# 1-Schematic_New_Project.net
KiCad netlist of a schematic drawn in EasyEDA
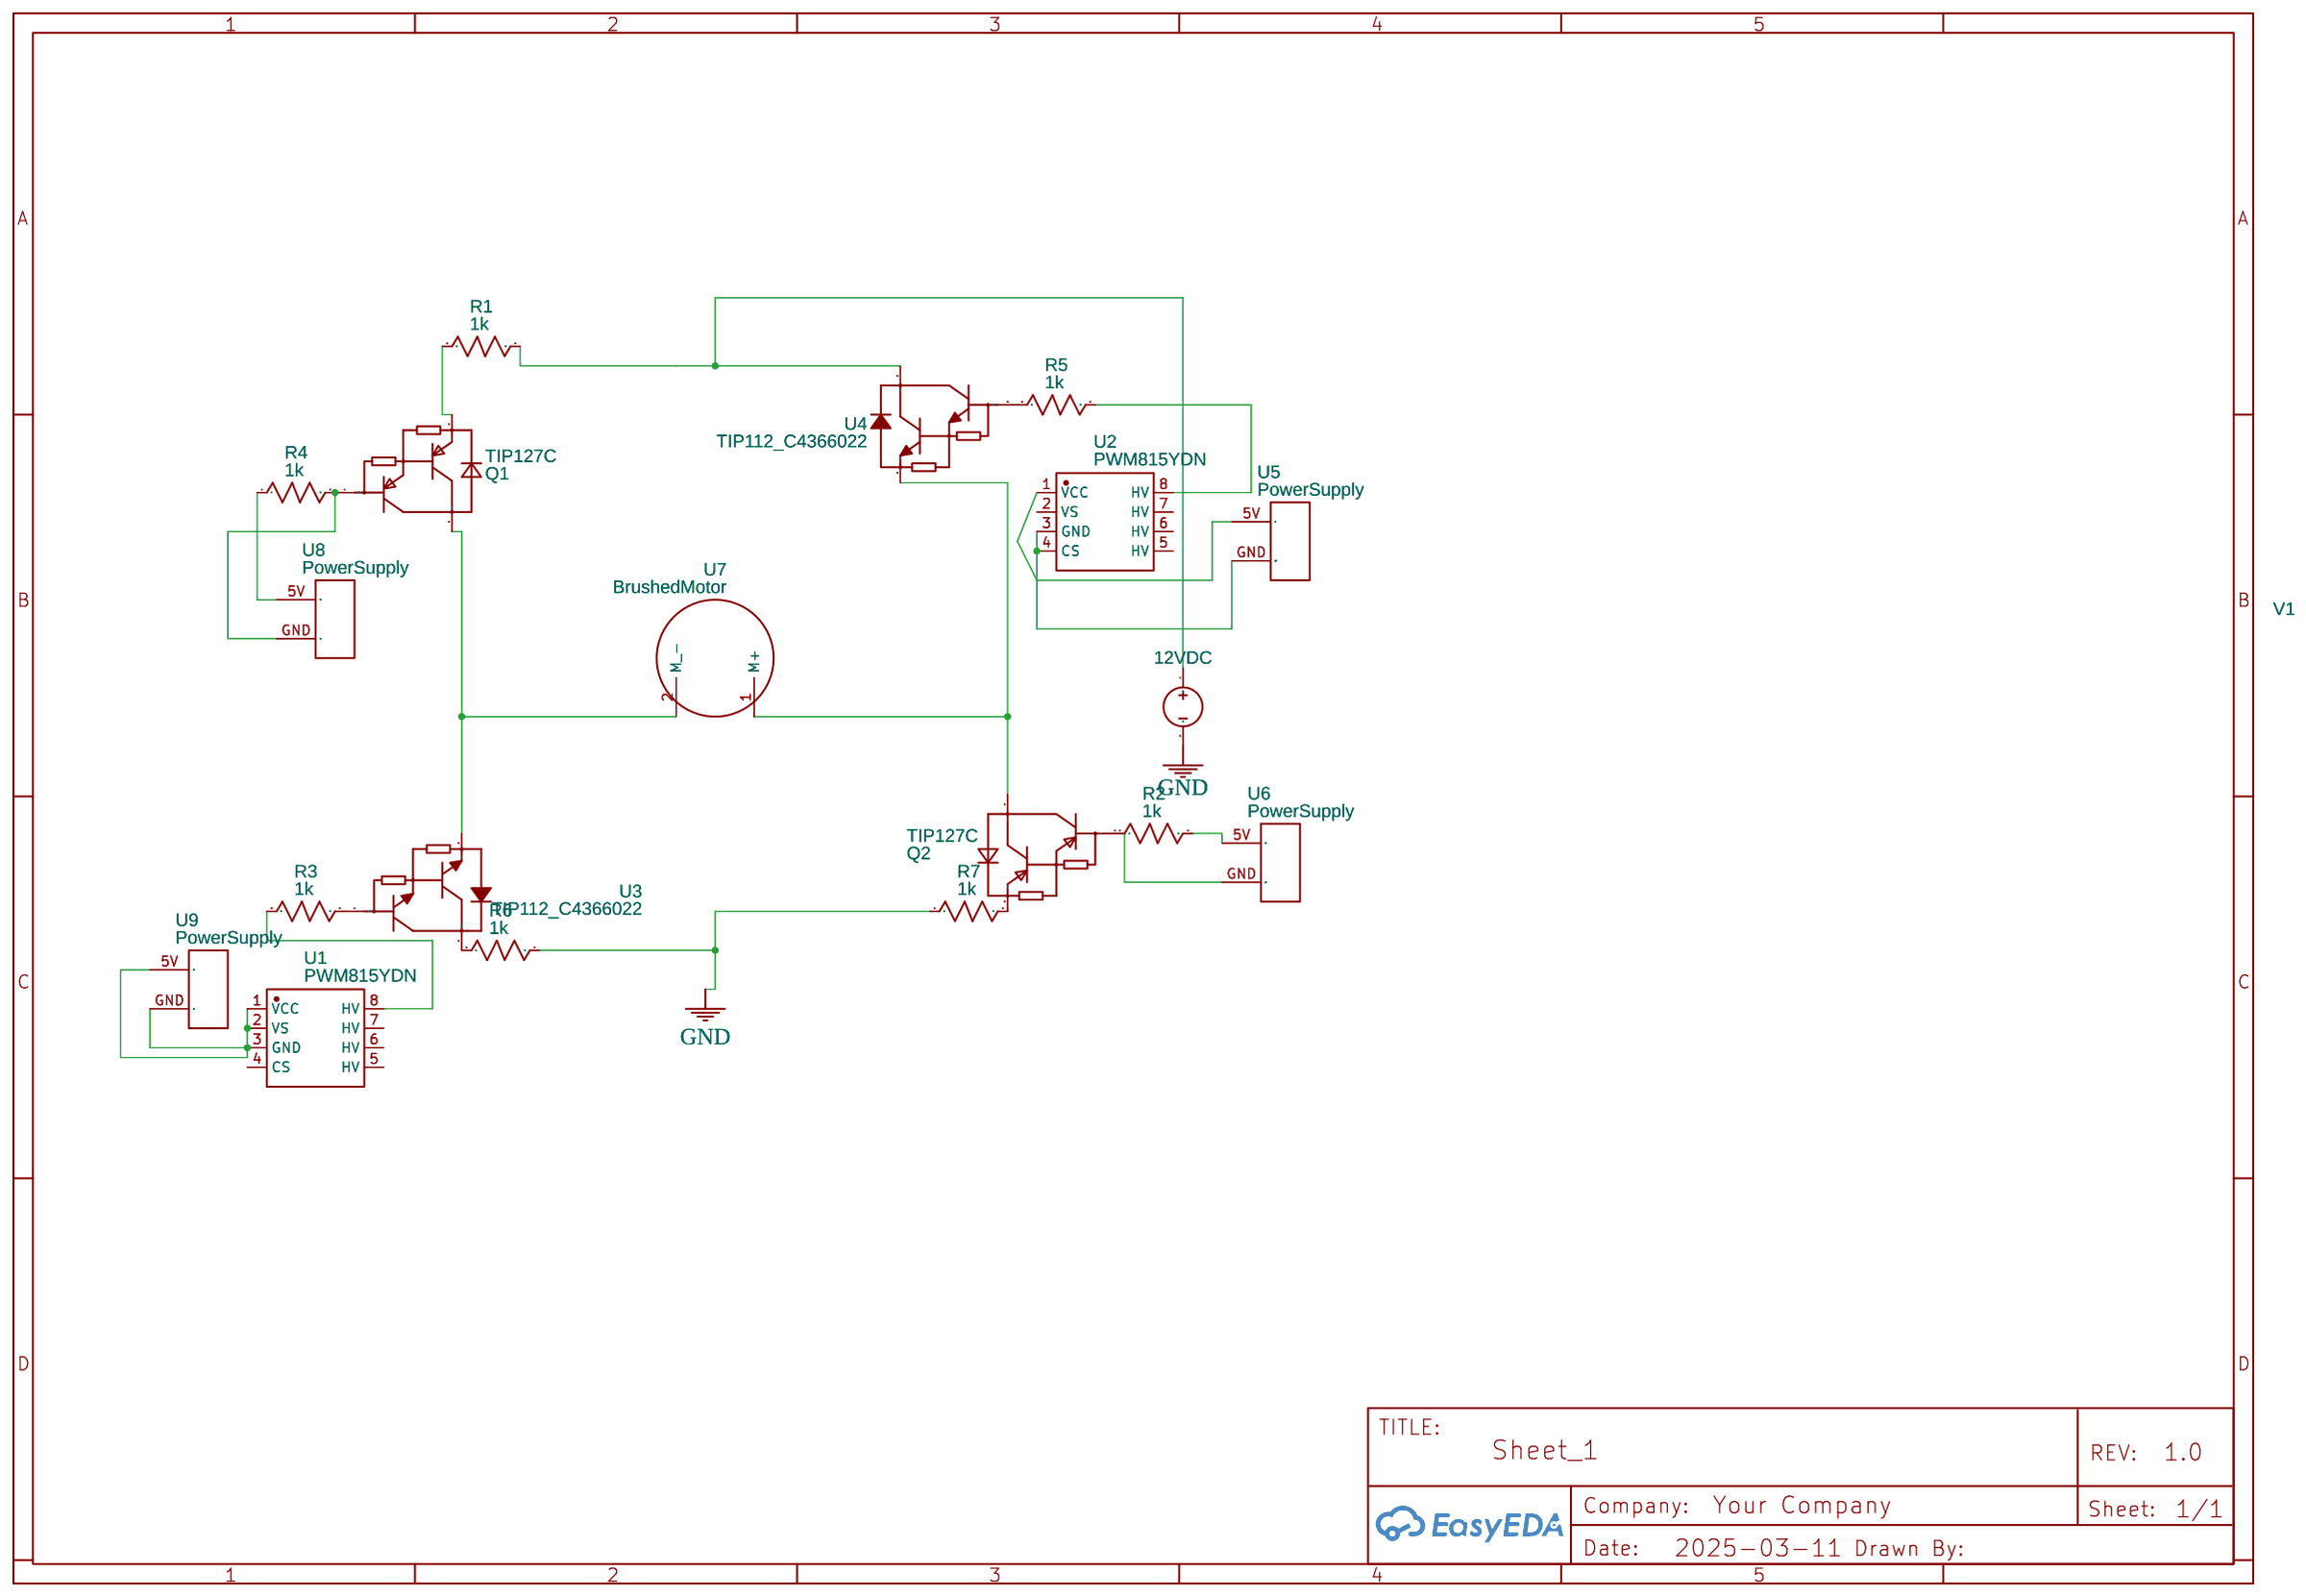
[diagram p0: schematic sheet]

(export (version "E")
  (design (tool "Eeschema 10.0.6"))
  (components
    (comp (ref "Q1")
      (value "TIP127C")
      (fields (field (name "Manufacturer") "FeiHong(飞虹)"))
      (libsource (lib "") (part "TIP127C_1"))
    )
    (comp (ref "Q2")
      (value "TIP127C")
      (fields (field (name "Manufacturer") "FeiHong(飞虹)"))
      (libsource (lib "") (part "TIP127C"))
    )
    (comp (ref "R1") (value "1k") (libsource (lib "") (part "R_0603_US")))
    (comp (ref "R2") (value "1k") (libsource (lib "") (part "R_0603_US")))
    (comp (ref "R3") (value "1k") (libsource (lib "") (part "R_0603_US")))
    (comp (ref "R4") (value "1k") (libsource (lib "") (part "R_0603_US")))
    (comp (ref "R5") (value "1k") (libsource (lib "") (part "R_0603_US")))
    (comp (ref "R6") (value "1k") (libsource (lib "") (part "R_0603_US")))
    (comp (ref "R7") (value "1k") (libsource (lib "") (part "R_0603_US")))
    (comp (ref "U1")
      (value "PWM815YDN")
      (fields (field (name "Manufacturer") "MASPOWER(麦思浦)"))
      (libsource (lib "") (part "PWM815YDN"))
    )
    (comp (ref "U2")
      (value "PWM815YDN")
      (fields (field (name "Manufacturer") "MASPOWER(麦思浦)"))
      (libsource (lib "") (part "PWM815YDN"))
    )
    (comp (ref "U3")
      (value "TIP112_C4366022")
      (fields (field (name "Manufacturer Part") "TIP112") (field (name "Manufacturer") "TI(德州仪器)"))
      (libsource (lib "") (part "TIP112_C4366022_1"))
    )
    (comp (ref "U4")
      (value "TIP112_C4366022")
      (fields (field (name "Manufacturer Part") "TIP112") (field (name "Manufacturer") "TI(德州仪器)"))
      (libsource (lib "") (part "TIP112_C4366022"))
    )
    (comp (ref "U5") (value "PowerSupply") (libsource (lib "") (part "PowerSupply")))
    (comp (ref "U6") (value "PowerSupply") (libsource (lib "") (part "PowerSupply")))
    (comp (ref "U7") (value "BrushedMotor") (libsource (lib "") (part "BrushedMotor")))
    (comp (ref "U8") (value "PowerSupply") (libsource (lib "") (part "PowerSupply")))
    (comp (ref "U9") (value "PowerSupply") (libsource (lib "") (part "PowerSupply")))
    (comp (ref "V1") (value "12VDC") (libsource (lib "") (part "Power_Supply_12V copy")))
  )
  (nets
    (net (code "1") (name "GND") (class "Default")
      (node (ref "R6") (pin "2") (pinfunction "2_2") (pintype "unspecified"))
      (node (ref "R7") (pin "1") (pinfunction "1_1") (pintype "unspecified"))
      (node (ref "V1") (pin "2") (pinfunction "2_2") (pintype "unspecified"))
    )
    (net (code "2") (name "Net-(Q1-B)") (class "Default")
      (node (ref "Q1") (pin "1") (pinfunction "B_1") (pintype "input"))
      (node (ref "R4") (pin "2") (pinfunction "2_2") (pintype "unspecified"))
      (node (ref "U8") (pin "GND") (pinfunction "GND_GND") (pintype "unspecified"))
    )
    (net (code "3") (name "Net-(Q1-C)") (class "Default")
      (node (ref "Q1") (pin "2") (pinfunction "C_2") (pintype "input"))
      (node (ref "U3") (pin "3") (pinfunction "E_3") (pintype "input"))
      (node (ref "U7") (pin "2") (pinfunction "M_-_2") (pintype "unspecified"))
    )
    (net (code "4") (name "Net-(Q1-E)") (class "Default")
      (node (ref "Q1") (pin "3") (pinfunction "E_3") (pintype "input"))
      (node (ref "R1") (pin "1") (pinfunction "1_1") (pintype "unspecified"))
    )
    (net (code "5") (name "Net-(Q2-B)") (class "Default")
      (node (ref "Q2") (pin "1") (pinfunction "B_1") (pintype "input"))
      (node (ref "U6") (pin "GND") (pinfunction "GND_GND") (pintype "unspecified"))
    )
    (net (code "6") (name "Net-(Q2-C)") (class "Default")
      (node (ref "Q2") (pin "2") (pinfunction "C_2") (pintype "input"))
      (node (ref "U4") (pin "3") (pinfunction "E_3") (pintype "input"))
      (node (ref "U7") (pin "1") (pinfunction "M+_1") (pintype "unspecified"))
    )
    (net (code "7") (name "Net-(Q2-E)") (class "Default")
      (node (ref "Q2") (pin "3") (pinfunction "E_3") (pintype "input"))
      (node (ref "R7") (pin "2") (pinfunction "2_2") (pintype "unspecified"))
    )
    (net (code "8") (name "Net-(R2-Pad2)") (class "Default")
      (node (ref "R2") (pin "2") (pinfunction "2_2") (pintype "unspecified"))
      (node (ref "U6") (pin "5V") (pinfunction "5V_5V") (pintype "unspecified"))
    )
    (net (code "9") (name "Net-(R3-Pad1)") (class "Default")
      (node (ref "R3") (pin "1") (pinfunction "1_1") (pintype "unspecified"))
      (node (ref "U1") (pin "8") (pinfunction "HV_8") (pintype "unspecified"))
    )
    (net (code "10") (name "Net-(R4-Pad1)") (class "Default")
      (node (ref "R4") (pin "1") (pinfunction "1_1") (pintype "unspecified"))
      (node (ref "U8") (pin "5V") (pinfunction "5V_5V") (pintype "unspecified"))
    )
    (net (code "11") (name "Net-(R5-Pad2)") (class "Default")
      (node (ref "R5") (pin "2") (pinfunction "2_2") (pintype "unspecified"))
      (node (ref "U2") (pin "8") (pinfunction "HV_8") (pintype "unspecified"))
    )
    (net (code "12") (name "Net-(U1-GND)") (class "Default")
      (node (ref "U1") (pin "1") (pinfunction "VCC_1") (pintype "unspecified"))
      (node (ref "U1") (pin "2") (pinfunction "VS_2") (pintype "unspecified"))
      (node (ref "U1") (pin "3") (pinfunction "GND_3") (pintype "unspecified"))
      (node (ref "U9") (pin "5V") (pinfunction "5V_5V") (pintype "unspecified"))
      (node (ref "U9") (pin "GND") (pinfunction "GND_GND") (pintype "unspecified"))
    )
    (net (code "13") (name "Net-(U2-CS)") (class "Default")
      (node (ref "U2") (pin "3") (pinfunction "GND_3") (pintype "unspecified"))
      (node (ref "U2") (pin "4") (pinfunction "CS_4") (pintype "unspecified"))
      (node (ref "U5") (pin "GND") (pinfunction "GND_GND") (pintype "unspecified"))
    )
    (net (code "14") (name "Net-(U2-VCC)") (class "Default")
      (node (ref "U2") (pin "1") (pinfunction "VCC_1") (pintype "unspecified"))
      (node (ref "U5") (pin "5V") (pinfunction "5V_5V") (pintype "unspecified"))
    )
    (net (code "15") (name "Net-(U3-B)") (class "Default")
      (node (ref "R3") (pin "2") (pinfunction "2_2") (pintype "unspecified"))
      (node (ref "U3") (pin "1") (pinfunction "B_1") (pintype "input"))
    )
    (net (code "16") (name "Net-(U3-C)") (class "Default")
      (node (ref "R6") (pin "1") (pinfunction "1_1") (pintype "unspecified"))
      (node (ref "U3") (pin "2") (pinfunction "C_2") (pintype "input"))
    )
    (net (code "17") (name "Net-(U4-B)") (class "Default")
      (node (ref "R5") (pin "1") (pinfunction "1_1") (pintype "unspecified"))
      (node (ref "U4") (pin "1") (pinfunction "B_1") (pintype "input"))
    )
    (net (code "18") (name "Net-(U4-C)") (class "Default")
      (node (ref "R1") (pin "2") (pinfunction "2_2") (pintype "unspecified"))
      (node (ref "U4") (pin "2") (pinfunction "C_2") (pintype "input"))
      (node (ref "V1") (pin "1") (pinfunction "1_1") (pintype "unspecified"))
    )
    (net (code "19") (name "unconnected-(R2-Pad1)") (class "Default")
      (node (ref "R2") (pin "1") (pinfunction "1_1") (pintype "unspecified"))
    )
    (net (code "20") (name "unconnected-(U1-CS-Pad4)") (class "Default")
      (node (ref "U1") (pin "4") (pinfunction "CS_4") (pintype "unspecified"))
    )
    (net (code "21") (name "unconnected-(U1-HV-Pad5)") (class "Default")
      (node (ref "U1") (pin "5") (pinfunction "HV_5") (pintype "unspecified"))
    )
    (net (code "22") (name "unconnected-(U1-HV-Pad6)") (class "Default")
      (node (ref "U1") (pin "6") (pinfunction "HV_6") (pintype "unspecified"))
    )
    (net (code "23") (name "unconnected-(U1-HV-Pad7)") (class "Default")
      (node (ref "U1") (pin "7") (pinfunction "HV_7") (pintype "unspecified"))
    )
    (net (code "24") (name "unconnected-(U2-HV-Pad5)") (class "Default")
      (node (ref "U2") (pin "5") (pinfunction "HV_5") (pintype "unspecified"))
    )
    (net (code "25") (name "unconnected-(U2-HV-Pad6)") (class "Default")
      (node (ref "U2") (pin "6") (pinfunction "HV_6") (pintype "unspecified"))
    )
    (net (code "26") (name "unconnected-(U2-HV-Pad7)") (class "Default")
      (node (ref "U2") (pin "7") (pinfunction "HV_7") (pintype "unspecified"))
    )
    (net (code "27") (name "unconnected-(U2-VS-Pad2)") (class "Default")
      (node (ref "U2") (pin "2") (pinfunction "VS_2") (pintype "unspecified"))
    )
  )
)
